# 01-MCU-USB.net
KiCad netlist of a schematic drawn in EasyEDA
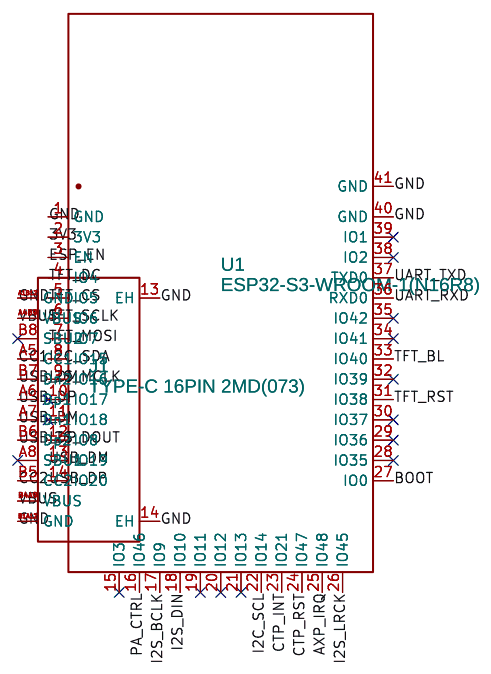
[diagram p0: schematic sheet]

(export (version "E")
  (design (tool "Eeschema 10.0.6"))
  (components
    (comp (ref "J1")
      (value "TYPE-C 16PIN 2MD(073)")
      (fields (field (name "Manufacturer") "SHOU HAN()"))
      (libsource (lib "") (part "Unknown_3935.0_3050.0"))
    )
    (comp (ref "U1")
      (value "ESP32-S3-WROOM-1(N16R8)")
      (fields
        (field (name "Manufacturer Part") "ESP32-S3-WROOM-1-N16R8")
        (field (name "Manufacturer") "ESPRESSIF()")
      )
      (libsource (lib "") (part "Unknown_4000.0_3000.0"))
    )
  )
  (nets
    (net (code "1") (name "/3V3") (class "Default")
      (node (ref "U1") (pin "2") (pinfunction "3V3_2") (pintype "unspecified"))
    )
    (net (code "2") (name "/AXP_IRQ") (class "Default")
      (node (ref "U1") (pin "25") (pinfunction "IO48_25") (pintype "unspecified"))
    )
    (net (code "3") (name "/BOOT") (class "Default")
      (node (ref "U1") (pin "27") (pinfunction "IO0_27") (pintype "unspecified"))
    )
    (net (code "4") (name "/CC1") (class "Default")
      (node (ref "J1") (pin "A5") (pinfunction "CC1_A5") (pintype "unspecified"))
    )
    (net (code "5") (name "/CC2") (class "Default")
      (node (ref "J1") (pin "B5") (pinfunction "CC2_B5") (pintype "unspecified"))
    )
    (net (code "6") (name "/CTP_INT") (class "Default")
      (node (ref "U1") (pin "23") (pinfunction "IO21_23") (pintype "unspecified"))
    )
    (net (code "7") (name "/CTP_RST") (class "Default")
      (node (ref "U1") (pin "24") (pinfunction "IO47_24") (pintype "unspecified"))
    )
    (net (code "8") (name "/ESP_EN") (class "Default")
      (node (ref "U1") (pin "3") (pinfunction "EN_3") (pintype "unspecified"))
    )
    (net (code "9") (name "/GND") (class "Default")
      (node (ref "J1") (pin "13") (pinfunction "EH_13") (pintype "unspecified"))
      (node (ref "J1") (pin "14") (pinfunction "EH_14") (pintype "unspecified"))
      (node (ref "J1") (pin "A1B12") (pinfunction "GND_A1B12") (pintype "unspecified"))
      (node (ref "J1") (pin "B1A12") (pinfunction "GND_B1A12") (pintype "unspecified"))
      (node (ref "U1") (pin "1") (pinfunction "GND_1") (pintype "unspecified"))
      (node (ref "U1") (pin "40") (pinfunction "GND_40") (pintype "unspecified"))
      (node (ref "U1") (pin "41") (pinfunction "GND_41") (pintype "unspecified"))
    )
    (net (code "10") (name "/I2C_SCL") (class "Default")
      (node (ref "U1") (pin "22") (pinfunction "IO14_22") (pintype "unspecified"))
    )
    (net (code "11") (name "/I2C_SDA") (class "Default")
      (node (ref "U1") (pin "8") (pinfunction "IO15_8") (pintype "unspecified"))
    )
    (net (code "12") (name "/I2S_BCLK") (class "Default")
      (node (ref "U1") (pin "17") (pinfunction "IO9_17") (pintype "unspecified"))
    )
    (net (code "13") (name "/I2S_DIN") (class "Default")
      (node (ref "U1") (pin "18") (pinfunction "IO10_18") (pintype "unspecified"))
    )
    (net (code "14") (name "/I2S_DOUT") (class "Default")
      (node (ref "U1") (pin "12") (pinfunction "IO8_12") (pintype "unspecified"))
    )
    (net (code "15") (name "/I2S_LRCK") (class "Default")
      (node (ref "U1") (pin "26") (pinfunction "IO45_26") (pintype "unspecified"))
    )
    (net (code "16") (name "/I2S_MCLK") (class "Default")
      (node (ref "U1") (pin "9") (pinfunction "IO16_9") (pintype "unspecified"))
    )
    (net (code "17") (name "/PA_CTRL") (class "Default")
      (node (ref "U1") (pin "16") (pinfunction "IO46_16") (pintype "unspecified"))
    )
    (net (code "18") (name "/TFT_BL") (class "Default")
      (node (ref "U1") (pin "33") (pinfunction "IO40_33") (pintype "unspecified"))
    )
    (net (code "19") (name "/TFT_CS") (class "Default")
      (node (ref "U1") (pin "5") (pinfunction "IO5_5") (pintype "unspecified"))
    )
    (net (code "20") (name "/TFT_DC") (class "Default")
      (node (ref "U1") (pin "4") (pinfunction "IO4_4") (pintype "unspecified"))
    )
    (net (code "21") (name "/TFT_MOSI") (class "Default")
      (node (ref "U1") (pin "7") (pinfunction "IO7_7") (pintype "unspecified"))
    )
    (net (code "22") (name "/TFT_RST") (class "Default")
      (node (ref "U1") (pin "31") (pinfunction "IO38_31") (pintype "unspecified"))
    )
    (net (code "23") (name "/TFT_SCLK") (class "Default")
      (node (ref "U1") (pin "6") (pinfunction "IO6_6") (pintype "unspecified"))
    )
    (net (code "24") (name "/UART_RXD") (class "Default")
      (node (ref "U1") (pin "36") (pinfunction "RXD0_36") (pintype "unspecified"))
    )
    (net (code "25") (name "/UART_TXD") (class "Default")
      (node (ref "U1") (pin "37") (pinfunction "TXD0_37") (pintype "unspecified"))
    )
    (net (code "26") (name "/USB_DM") (class "Default")
      (node (ref "J1") (pin "A7") (pinfunction "Dn1_A7") (pintype "unspecified"))
      (node (ref "J1") (pin "B7") (pinfunction "Dn2_B7") (pintype "unspecified"))
      (node (ref "U1") (pin "13") (pinfunction "IO19_13") (pintype "unspecified"))
    )
    (net (code "27") (name "/USB_DP") (class "Default")
      (node (ref "J1") (pin "A6") (pinfunction "Dp1_A6") (pintype "unspecified"))
      (node (ref "J1") (pin "B6") (pinfunction "Dp2_B6") (pintype "unspecified"))
      (node (ref "U1") (pin "14") (pinfunction "IO20_14") (pintype "unspecified"))
    )
    (net (code "28") (name "/VBUS") (class "Default")
      (node (ref "J1") (pin "A4B9") (pinfunction "VBUS_A4B9") (pintype "unspecified"))
      (node (ref "J1") (pin "B4A9") (pinfunction "VBUS_B4A9") (pintype "unspecified"))
    )
    (net (code "29") (name "unconnected-(J1-SBU1-PadA8)") (class "Default")
      (node (ref "J1") (pin "A8") (pinfunction "SBU1_A8") (pintype "unspecified+no_connect"))
    )
    (net (code "30") (name "unconnected-(J1-SBU2-PadB8)") (class "Default")
      (node (ref "J1") (pin "B8") (pinfunction "SBU2_B8") (pintype "unspecified+no_connect"))
    )
    (net (code "31") (name "unconnected-(U1-IO1-Pad39)") (class "Default")
      (node (ref "U1") (pin "39") (pinfunction "IO1_39") (pintype "unspecified+no_connect"))
    )
    (net (code "32") (name "unconnected-(U1-IO2-Pad38)") (class "Default")
      (node (ref "U1") (pin "38") (pinfunction "IO2_38") (pintype "unspecified+no_connect"))
    )
    (net (code "33") (name "unconnected-(U1-IO3-Pad15)") (class "Default")
      (node (ref "U1") (pin "15") (pinfunction "IO3_15") (pintype "unspecified+no_connect"))
    )
    (net (code "34") (name "unconnected-(U1-IO11-Pad19)") (class "Default")
      (node (ref "U1") (pin "19") (pinfunction "IO11_19") (pintype "unspecified+no_connect"))
    )
    (net (code "35") (name "unconnected-(U1-IO12-Pad20)") (class "Default")
      (node (ref "U1") (pin "20") (pinfunction "IO12_20") (pintype "unspecified+no_connect"))
    )
    (net (code "36") (name "unconnected-(U1-IO13-Pad21)") (class "Default")
      (node (ref "U1") (pin "21") (pinfunction "IO13_21") (pintype "unspecified+no_connect"))
    )
    (net (code "37") (name "unconnected-(U1-IO17-Pad10)") (class "Default")
      (node (ref "U1") (pin "10") (pinfunction "IO17_10") (pintype "unspecified+no_connect"))
    )
    (net (code "38") (name "unconnected-(U1-IO18-Pad11)") (class "Default")
      (node (ref "U1") (pin "11") (pinfunction "IO18_11") (pintype "unspecified+no_connect"))
    )
    (net (code "39") (name "unconnected-(U1-IO35-Pad28)") (class "Default")
      (node (ref "U1") (pin "28") (pinfunction "IO35_28") (pintype "unspecified+no_connect"))
    )
    (net (code "40") (name "unconnected-(U1-IO36-Pad29)") (class "Default")
      (node (ref "U1") (pin "29") (pinfunction "IO36_29") (pintype "unspecified+no_connect"))
    )
    (net (code "41") (name "unconnected-(U1-IO37-Pad30)") (class "Default")
      (node (ref "U1") (pin "30") (pinfunction "IO37_30") (pintype "unspecified+no_connect"))
    )
    (net (code "42") (name "unconnected-(U1-IO39-Pad32)") (class "Default")
      (node (ref "U1") (pin "32") (pinfunction "IO39_32") (pintype "unspecified+no_connect"))
    )
    (net (code "43") (name "unconnected-(U1-IO41-Pad34)") (class "Default")
      (node (ref "U1") (pin "34") (pinfunction "IO41_34") (pintype "unspecified+no_connect"))
    )
    (net (code "44") (name "unconnected-(U1-IO42-Pad35)") (class "Default")
      (node (ref "U1") (pin "35") (pinfunction "IO42_35") (pintype "unspecified+no_connect"))
    )
  )
)
